# schematic.net
KiCad netlist of a schematic drawn in EasyEDA
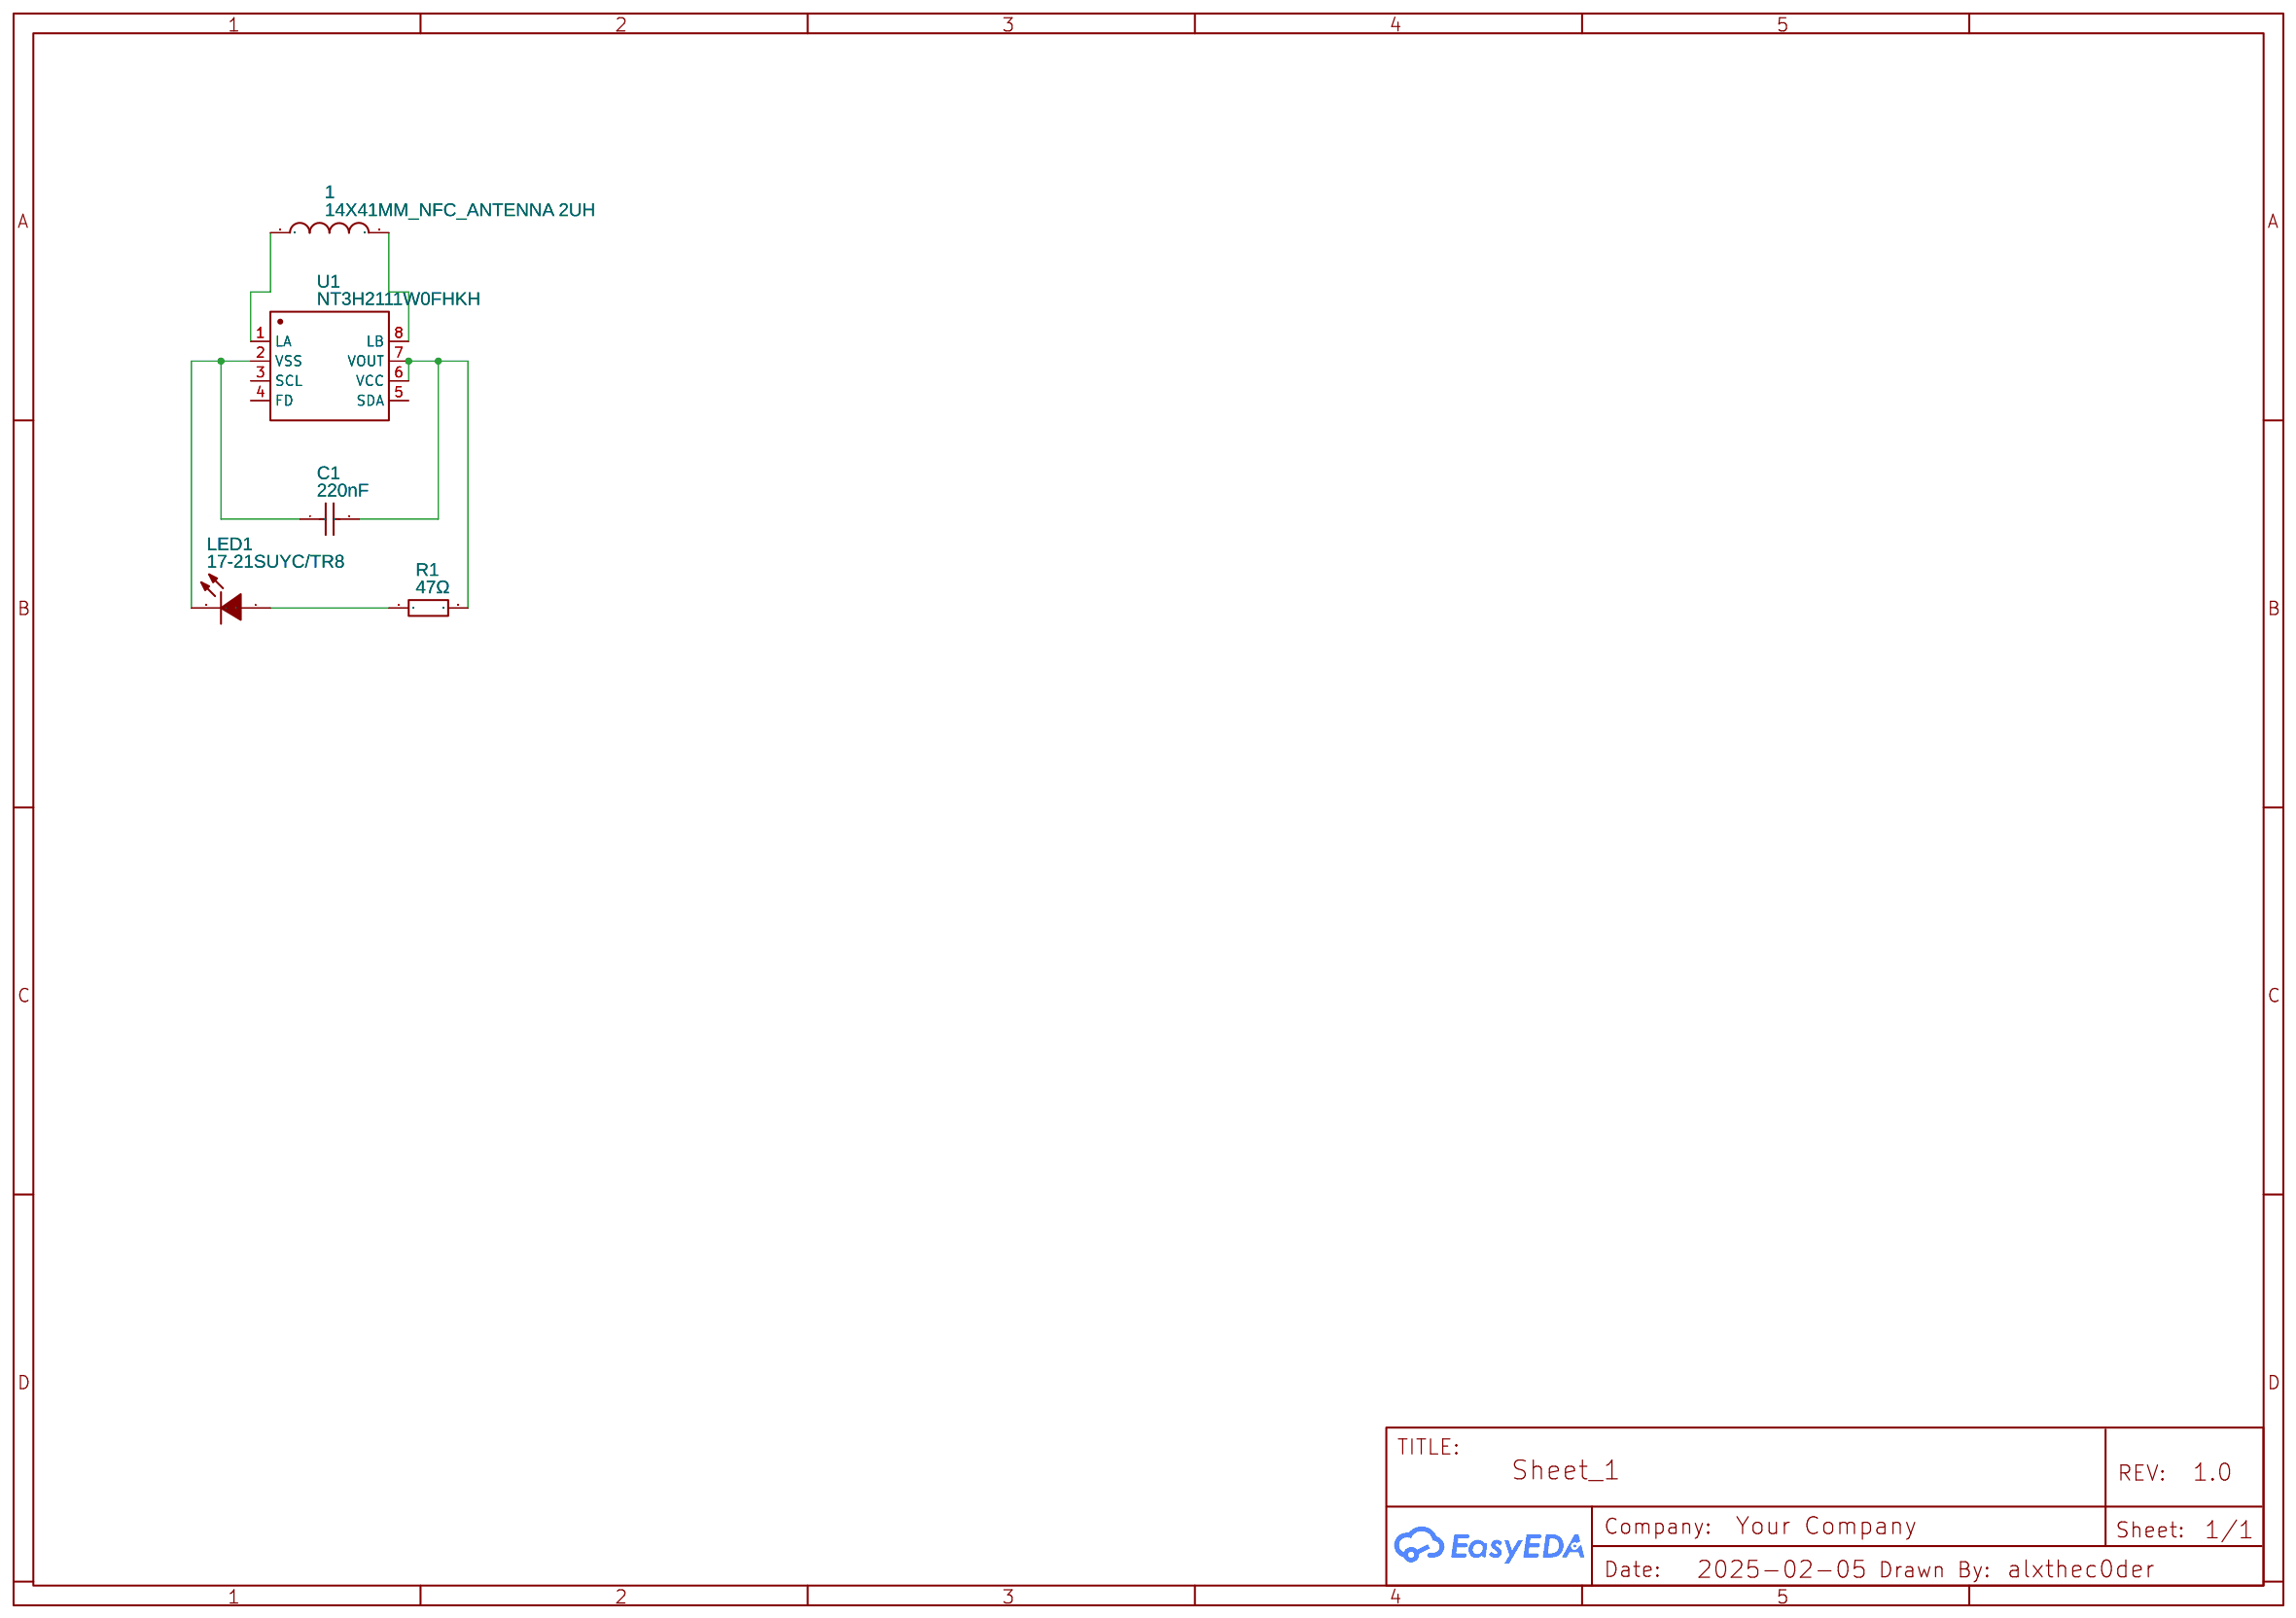
[diagram p0: schematic sheet]

(export (version "E")
  (design (tool "Eeschema 10.0.6"))
  (components
    (comp (ref "1") (value "14X41MM_NFC_ANTENNA 2UH") (libsource (lib "") (part "14X41MM_NFC_ANTENNA 2UH")))
    (comp (ref "C1")
      (value "220nF")
      (fields
        (field (name "Manufacturer Part") "CL10B224KA8NNNC")
        (field (name "Manufacturer") "SAMSUNG(三星)")
      )
      (libsource (lib "") (part "CL10B224KA8NNNC"))
    )
    (comp (ref "LED1")
      (value "17-21SUYC/TR8")
      (fields (field (name "Manufacturer Part") "KT-0805黄灯") (field (name "Manufacturer") "KENTO"))
      (libsource (lib "") (part "17-21SUYC/TR8"))
    )
    (comp (ref "R1")
      (value "47Ω")
      (fields
        (field (name "Manufacturer Part") "0603WAF470JT5E")
        (field (name "Manufacturer") "UNI-ROYAL(厚声)")
      )
      (libsource (lib "") (part "0603WAF470JT5E"))
    )
    (comp (ref "U1")
      (value "NT3H2111W0FHKH")
      (fields (field (name "Manufacturer") "NXP(恩智浦)"))
      (libsource (lib "") (part "NT3H2111W0FHKH"))
    )
  )
  (nets
    (net (code "1") (name "Net-(LED1-+)") (class "Default")
      (node (ref "LED1") (pin "1") (pinfunction "+_1") (pintype "unspecified"))
      (node (ref "R1") (pin "1") (pinfunction "1_1") (pintype "input"))
    )
    (net (code "2") (name "Net-(LED1--)") (class "Default")
      (node (ref "C1") (pin "1") (pinfunction "1_1") (pintype "input"))
      (node (ref "LED1") (pin "2") (pinfunction "-_2") (pintype "unspecified"))
      (node (ref "U1") (pin "2") (pinfunction "VSS_2") (pintype "unspecified"))
    )
    (net (code "3") (name "Net-(U1-LA)") (class "Default")
      (node (ref "1") (pin "P$1") (pinfunction "P$1_P$1") (pintype "bidirectional"))
      (node (ref "U1") (pin "1") (pinfunction "LA_1") (pintype "unspecified"))
    )
    (net (code "4") (name "Net-(U1-LB)") (class "Default")
      (node (ref "1") (pin "P$2") (pinfunction "P$2_P$2") (pintype "bidirectional"))
      (node (ref "U1") (pin "8") (pinfunction "LB_8") (pintype "unspecified"))
    )
    (net (code "5") (name "Net-(U1-VCC)") (class "Default")
      (node (ref "C1") (pin "2") (pinfunction "2_2") (pintype "input"))
      (node (ref "R1") (pin "2") (pinfunction "2_2") (pintype "input"))
      (node (ref "U1") (pin "6") (pinfunction "VCC_6") (pintype "unspecified"))
      (node (ref "U1") (pin "7") (pinfunction "VOUT_7") (pintype "unspecified"))
    )
    (net (code "6") (name "unconnected-(U1-FD-Pad4)") (class "Default")
      (node (ref "U1") (pin "4") (pinfunction "FD_4") (pintype "unspecified"))
    )
    (net (code "7") (name "unconnected-(U1-SCL-Pad3)") (class "Default")
      (node (ref "U1") (pin "3") (pinfunction "SCL_3") (pintype "unspecified"))
    )
    (net (code "8") (name "unconnected-(U1-SDA-Pad5)") (class "Default")
      (node (ref "U1") (pin "5") (pinfunction "SDA_5") (pintype "unspecified"))
    )
  )
)
